# 411_Preliminary_Design__Group8_rev4_6.net
KiCad netlist of a schematic drawn in EAGLE
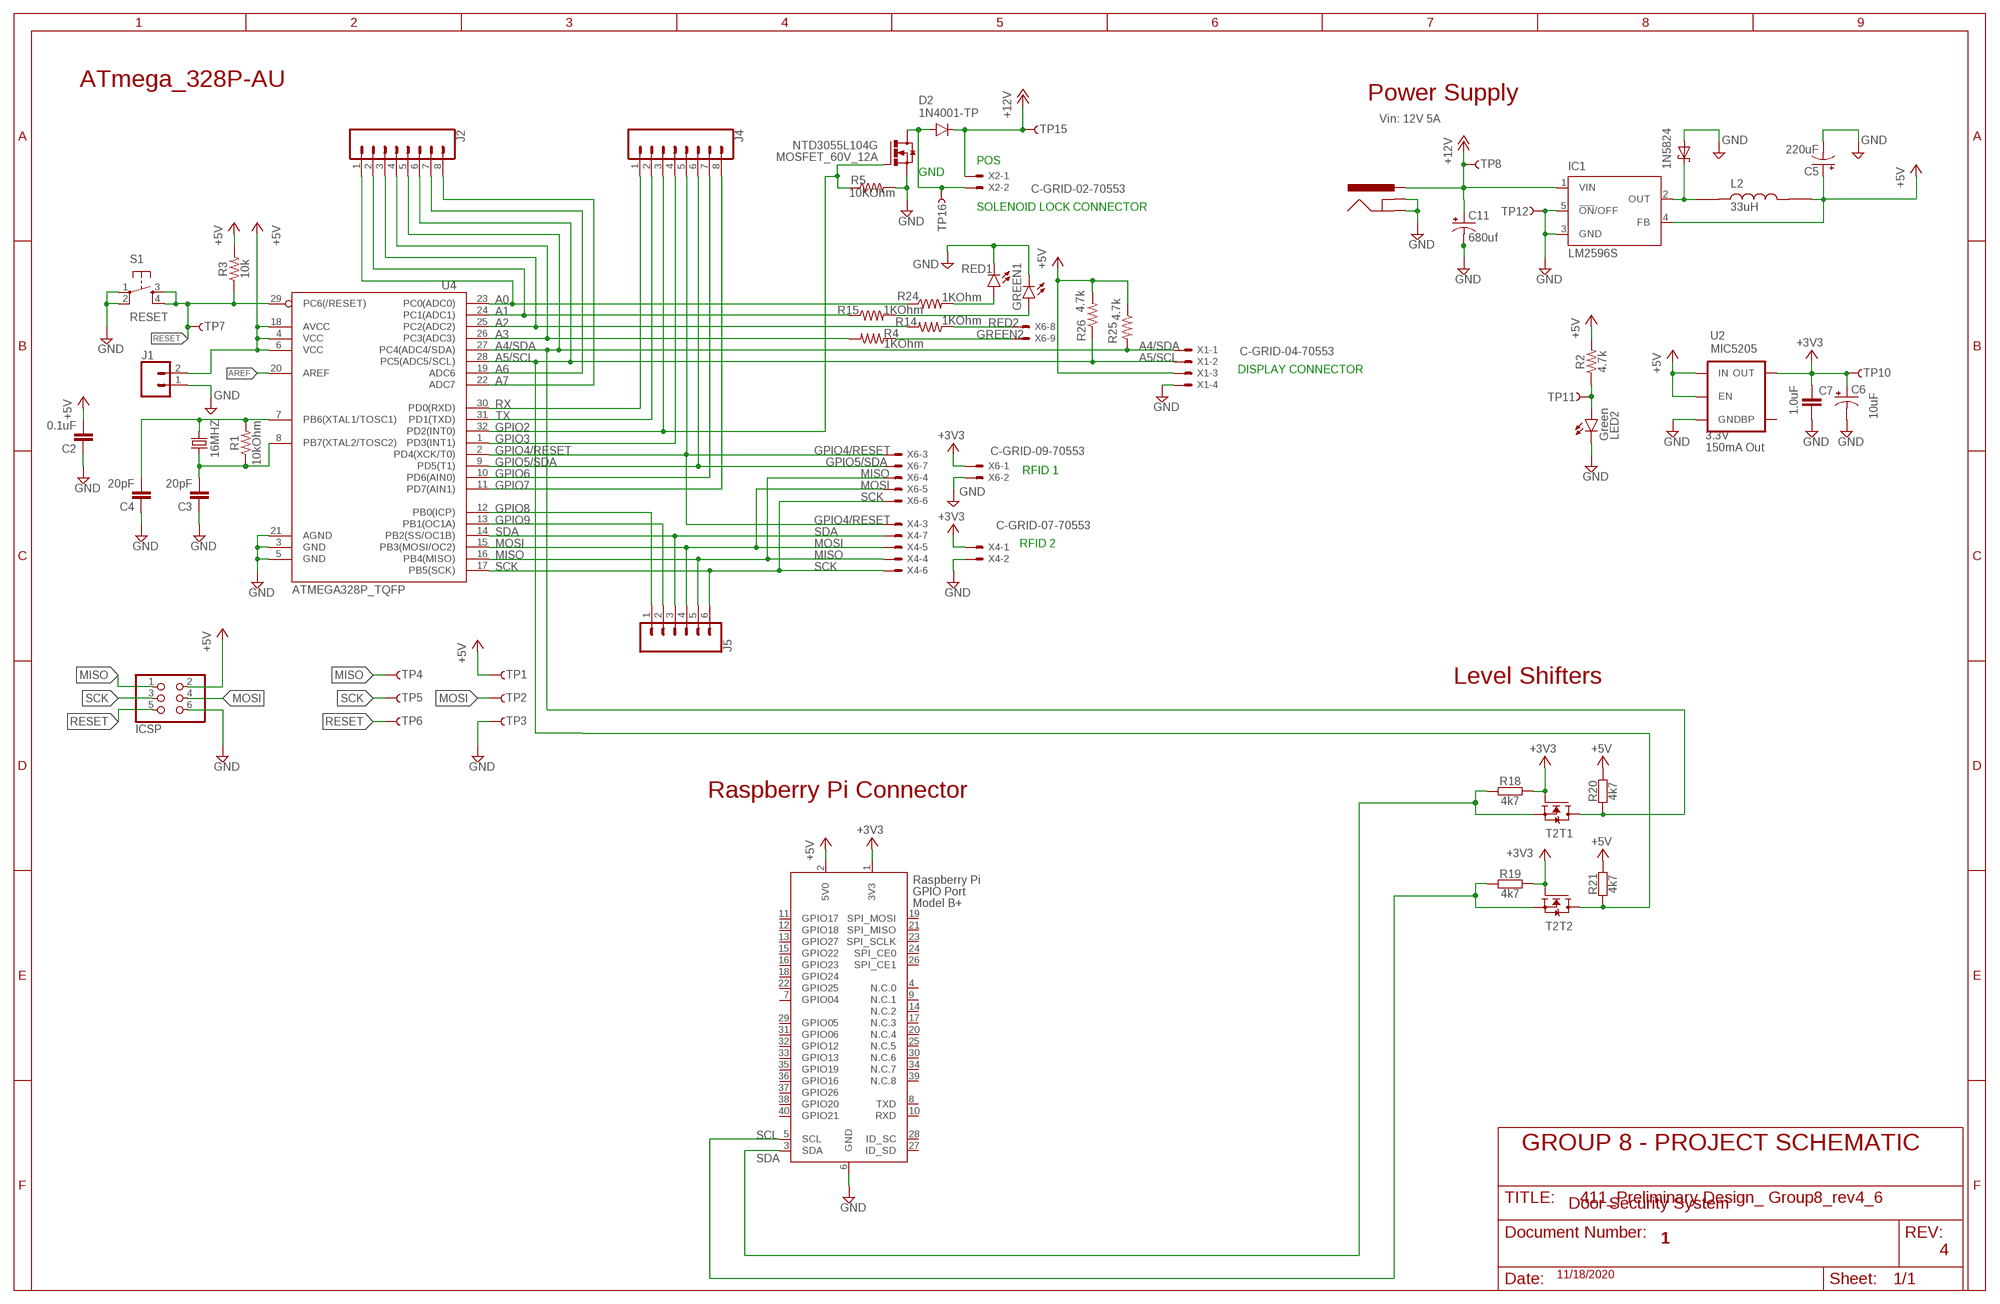
[diagram p0: schematic, sheet 1]

(export (version "E")
  (design (tool "Eeschema 10.0.6"))
  (components
    (comp (ref "1N5824")
      (value "SCHOTTKY-DIODECB429-15")
      (footprint "eagle-import:CB429-15")
      (libsource (lib "eagle-import") (part "SCHOTTKY-DIODECB429-15"))
    )
    (comp (ref "16MHZ")
      (value "16MHZ")
      (footprint "eagle-import:HC49_S")
      (libsource (lib "eagle-import") (part "CRYSTALHC49S"))
    )
    (comp (ref "C2")
      (value "0.1uF")
      (footprint "eagle-import:0603")
      (libsource (lib "eagle-import") (part "0.1UF-0603-25V-(+80/-20%)"))
    )
    (comp (ref "C3")
      (value "20pF")
      (footprint "eagle-import:0603")
      (libsource (lib "eagle-import") (part "0.1UF-0603-25V-(+80/-20%)"))
    )
    (comp (ref "C4")
      (value "20pF")
      (footprint "eagle-import:0603")
      (libsource (lib "eagle-import") (part "0.1UF-0603-25V-(+80/-20%)"))
    )
    (comp (ref "C5")
      (value "220uF")
      (footprint "eagle-import:153CLV-0605")
      (libsource (lib "eagle-import") (part "CPOL-US153CLV-0605"))
    )
    (comp (ref "C6")
      (value "10uF")
      (footprint "eagle-import:EIA3216")
      (libsource (lib "eagle-import") (part "10UF-POLAR-EIA3216-16V-10%(TANT)"))
    )
    (comp (ref "C7")
      (value "1.0uF")
      (footprint "eagle-import:0603")
      (libsource (lib "eagle-import") (part "1.0UF-0603-16V-10%"))
    )
    (comp (ref "C11")
      (value "680uf")
      (footprint "eagle-import:153CLV-0605")
      (libsource (lib "eagle-import") (part "CPOL-US153CLV-0605"))
    )
    (comp (ref "D2")
      (value "1N4001-TP")
      (footprint "eagle-import:DO41-10")
      (libsource (lib "eagle-import") (part "1N4004"))
    )
    (comp (ref "GREEN1")
      (value "LED5MM")
      (footprint "eagle-import:LED5MM")
      (libsource (lib "eagle-import") (part "led_259_LED5MM"))
    )
    (comp (ref "IC1")
      (value "LM2596S")
      (footprint "eagle-import:TO263-5")
      (fields (field (name "MF") "NATIONAL SEMICONDUCTOR") (field (name "MPN") "LM2596S-ADJ/NOPB"))
      (libsource (lib "eagle-import") (part "LM2596S"))
    )
    (comp (ref "ICSP")
      (value "ICSP")
      (footprint "eagle-import:2X03")
      (libsource (lib "eagle-import") (part "PINHD-2X3"))
    )
    (comp (ref "J1")
      (value "CONN_02")
      (footprint "eagle-import:1X02")
      (libsource (lib "eagle-import") (part "CONN_02"))
    )
    (comp (ref "J2")
      (value "CONN_08\"")
      (footprint "eagle-import:1X08")
      (libsource (lib "eagle-import") (part "CONN_08{dblquote}"))
    )
    (comp (ref "J3")
      (value "POWER_JACKSUPER_BOMB_DIGITY")
      (footprint "eagle-import:POWER_JACK_SMD_OVERPASTE_SUPER_BOMB_DIGITY")
      (libsource (lib "eagle-import") (part "POWER_JACKSUPER_BOMB_DIGITY"))
    )
    (comp (ref "J4")
      (value "CONN_08\"")
      (footprint "eagle-import:1X08")
      (libsource (lib "eagle-import") (part "CONN_08{dblquote}"))
    )
    (comp (ref "J5")
      (value "CONN_06SILK_FEMALE_PTH")
      (footprint "eagle-import:1X06")
      (libsource (lib "eagle-import") (part "CONN_06SILK_FEMALE_PTH"))
    )
    (comp (ref "L2")
      (value "33uH")
      (footprint "eagle-import:IND_#B953AS-330M=P3")
      (fields
        (field (name "DIGI-KEY_PART_NUMBER") "490-14099-1-ND")
        (field (name "MF") "Murata")
        (field (name "MP") "#B953AS-330M=P3")
      )
      (libsource (lib "eagle-import") (part "#B953AS-330M=P3"))
    )
    (comp (ref "LED2")
      (value "Green")
      (footprint "eagle-import:LED-1206")
      (libsource (lib "eagle-import") (part "LED1206"))
    )
    (comp (ref "MOSFET_60V_12A")
      (value "NTD3055L104G")
      (footprint "eagle-import:DPAK3")
      (fields (field (name "MANUFACTURER") "ON SEMICONDUCTORS") (field (name "CREATED_BY") "PCBLayout.com"))
      (libsource (lib "eagle-import") (part "NTD3055L104G"))
    )
    (comp (ref "R1")
      (value "10kOhm")
      (footprint "eagle-import:0603")
      (libsource (lib "eagle-import") (part "10KOHM-0603-1/10W-1%"))
    )
    (comp (ref "R2")
      (value "4.7k")
      (footprint "eagle-import:0603")
      (libsource (lib "eagle-import") (part "4.7KOHM-0603-1/10W-1%"))
    )
    (comp (ref "R3")
      (value "10k")
      (footprint "eagle-import:0603")
      (libsource (lib "eagle-import") (part "10KOHM-0603-1/10W-1%"))
    )
    (comp (ref "R4")
      (value "1KOhm")
      (footprint "eagle-import:M1406")
      (libsource (lib "eagle-import") (part "R-US_M1406"))
    )
    (comp (ref "R5")
      (value "10KOhm")
      (footprint "eagle-import:M1406")
      (libsource (lib "eagle-import") (part "R-US_M1406"))
    )
    (comp (ref "R14")
      (value "1KOhm")
      (footprint "eagle-import:M1406")
      (libsource (lib "eagle-import") (part "R-US_M1406"))
    )
    (comp (ref "R15")
      (value "1KOhm")
      (footprint "eagle-import:M1406")
      (libsource (lib "eagle-import") (part "R-US_M1406"))
    )
    (comp (ref "R18")
      (value "4k7")
      (footprint "eagle-import:C0402")
      (libsource (lib "eagle-import") (part "RESISTOR-0402"))
    )
    (comp (ref "R19")
      (value "4k7")
      (footprint "eagle-import:C0402")
      (libsource (lib "eagle-import") (part "RESISTOR-0402"))
    )
    (comp (ref "R20")
      (value "4k7")
      (footprint "eagle-import:C0402")
      (libsource (lib "eagle-import") (part "RESISTOR-0402"))
    )
    (comp (ref "R21")
      (value "4k7")
      (footprint "eagle-import:C0402")
      (libsource (lib "eagle-import") (part "RESISTOR-0402"))
    )
    (comp (ref "R24")
      (value "1KOhm")
      (footprint "eagle-import:M1406")
      (libsource (lib "eagle-import") (part "R-US_M1406"))
    )
    (comp (ref "R25")
      (value "4.7k")
      (footprint "eagle-import:0603")
      (libsource (lib "eagle-import") (part "4.7KOHM-0603-1/10W-1%"))
    )
    (comp (ref "R26")
      (value "4.7k")
      (footprint "eagle-import:0603")
      (libsource (lib "eagle-import") (part "4.7KOHM-0603-1/10W-1%"))
    )
    (comp (ref "RED1")
      (value "LED5MM")
      (footprint "eagle-import:LED5MM")
      (fields (field (name "SPICEPREFIX") "L"))
      (libsource (lib "eagle-import") (part "led_259_LED5MM"))
    )
    (comp (ref "S1")
      (value "RESET")
      (footprint "eagle-import:TACTILE-SWITCH-SMD")
      (libsource (lib "eagle-import") (part "SWITCH_SPST_4_PINSQUARE"))
    )
    (comp (ref "T2")
      (value "BSS138PS")
      (footprint "eagle-import:SOT363")
      (libsource (lib "eagle-import") (part "BSS138PS"))
    )
    (comp (ref "TP1")
      (value "TP-3x5")
      (footprint "eagle-import:PAD.03X.05")
      (libsource (lib "eagle-import") (part "TEST-POINT3X5"))
    )
    (comp (ref "TP2")
      (value "TP-3x5")
      (footprint "eagle-import:PAD.03X.05")
      (libsource (lib "eagle-import") (part "TEST-POINT3X5"))
    )
    (comp (ref "TP3")
      (value "TP-3x5")
      (footprint "eagle-import:PAD.03X.05")
      (libsource (lib "eagle-import") (part "TEST-POINT3X5"))
    )
    (comp (ref "TP4")
      (value "TP-3x5")
      (footprint "eagle-import:PAD.03X.05")
      (libsource (lib "eagle-import") (part "TEST-POINT3X5"))
    )
    (comp (ref "TP5")
      (value "TP-3x5")
      (footprint "eagle-import:PAD.03X.05")
      (libsource (lib "eagle-import") (part "SparkFun-Passives_TEST-POINT3X5"))
    )
    (comp (ref "TP6")
      (value "TP-3x5")
      (footprint "eagle-import:PAD.03X.05")
      (libsource (lib "eagle-import") (part "TEST-POINT3X5"))
    )
    (comp (ref "TP7")
      (value "TP-3x5")
      (footprint "eagle-import:PAD.03X.05")
      (libsource (lib "eagle-import") (part "TEST-POINT3X5"))
    )
    (comp (ref "TP8")
      (value "TP-3x5")
      (footprint "eagle-import:PAD.03X.05")
      (libsource (lib "eagle-import") (part "TEST-POINT3X5"))
    )
    (comp (ref "TP10")
      (value "TP-3x5")
      (footprint "eagle-import:PAD.03X.05")
      (libsource (lib "eagle-import") (part "TEST-POINT3X5"))
    )
    (comp (ref "TP11")
      (value "TP-3x5")
      (footprint "eagle-import:PAD.03X.05")
      (libsource (lib "eagle-import") (part "TEST-POINT3X5"))
    )
    (comp (ref "TP12")
      (value "TP-3x5")
      (footprint "eagle-import:PAD.03X.05")
      (libsource (lib "eagle-import") (part "TEST-POINT3X5"))
    )
    (comp (ref "TP15")
      (value "TP-3x5")
      (footprint "eagle-import:PAD.03X.05")
      (libsource (lib "eagle-import") (part "TEST-POINT3X5"))
    )
    (comp (ref "TP16")
      (value "TP-3x5")
      (footprint "eagle-import:PAD.03X.05")
      (libsource (lib "eagle-import") (part "TEST-POINT3X5"))
    )
    (comp (ref "U2")
      (value "MIC5205")
      (footprint "eagle-import:SOT23-5")
      (libsource (lib "eagle-import") (part "MIC52053.3V"))
    )
    (comp (ref "U4")
      (value "ATMEGA328P_TQFP")
      (footprint "eagle-import:TQFP32-08")
      (libsource (lib "eagle-import") (part "ATMEGA328P_TQFP"))
    )
    (comp (ref "X1")
      (value "C-GRID-04-70553")
      (footprint "eagle-import:70553-04")
      (fields (field (name "MF") "MOLEX"))
      (libsource (lib "eagle-import") (part "C-GRID-04-70553"))
    )
    (comp (ref "X2")
      (value "C-GRID-02-70553")
      (footprint "eagle-import:70553-02")
      (fields (field (name "MF") "MOLEX"))
      (libsource (lib "eagle-import") (part "C-GRID-02-70553"))
    )
    (comp (ref "X4")
      (value "C-GRID-07-70553")
      (footprint "eagle-import:70553-07")
      (fields (field (name "MF") "MOLEX"))
      (libsource (lib "eagle-import") (part "C-GRID-07-70553"))
    )
    (comp (ref "X5")
      (value "RASPI_BOARD_B+_E4P")
      (footprint "eagle-import:RASPI_BOARD_B+_EDGES_4DRILL_PAD")
      (libsource (lib "eagle-import") (part "RASPI_BOARD_B+_E4P"))
    )
    (comp (ref "X6")
      (value "C-GRID-09-70553")
      (footprint "eagle-import:70553-09")
      (fields (field (name "MF") "MOLEX"))
      (libsource (lib "eagle-import") (part "C-GRID-09-70553"))
    )
  )
  (nets
    (net (code "1") (name "+3V3") (class "Default")
      (node (ref "C6") (pin "+") (pinfunction "+_+") (pintype "passive"))
      (node (ref "C7") (pin "1") (pinfunction "1_1") (pintype "passive"))
      (node (ref "R18") (pin "2") (pinfunction "2_2") (pintype "passive"))
      (node (ref "R19") (pin "2") (pinfunction "2_2") (pintype "passive"))
      (node (ref "T2") (pin "2") (pinfunction "G_2") (pintype "passive"))
      (node (ref "T2") (pin "5") (pinfunction "G_5") (pintype "passive"))
      (node (ref "TP10") (pin "P$1") (pinfunction "1_P$1") (pintype "bidirectional"))
      (node (ref "U2") (pin "5") (pinfunction "OUT_5") (pintype "passive"))
      (node (ref "X4") (pin "1") (pinfunction "S_1") (pintype "passive"))
      (node (ref "X5") (pin "1") (pinfunction "3V3_1") (pintype "power_in"))
      (node (ref "X6") (pin "1") (pinfunction "S_1") (pintype "passive"))
    )
    (net (code "2") (name "+5V") (class "Default")
      (node (ref "C2") (pin "2") (pinfunction "2_2") (pintype "passive"))
      (node (ref "C5") (pin "+") (pinfunction "+_+") (pintype "passive"))
      (node (ref "IC1") (pin "4") (pinfunction "FB_4") (pintype "input"))
      (node (ref "ICSP") (pin "2") (pinfunction "2_2") (pintype "passive"))
      (node (ref "J1") (pin "2") (pinfunction "2_2") (pintype "passive"))
      (node (ref "L2") (pin "2") (pinfunction "2_2") (pintype "passive"))
      (node (ref "R2") (pin "2") (pinfunction "2_2") (pintype "passive"))
      (node (ref "R20") (pin "2") (pinfunction "2_2") (pintype "passive"))
      (node (ref "R21") (pin "2") (pinfunction "2_2") (pintype "passive"))
      (node (ref "R25") (pin "1") (pinfunction "1_1") (pintype "passive"))
      (node (ref "R26") (pin "2") (pinfunction "2_2") (pintype "passive"))
      (node (ref "R3") (pin "2") (pinfunction "2_2") (pintype "passive"))
      (node (ref "TP1") (pin "P$1") (pinfunction "1_P$1") (pintype "bidirectional"))
      (node (ref "U2") (pin "1") (pinfunction "IN_1") (pintype "input"))
      (node (ref "U2") (pin "3") (pinfunction "EN_3") (pintype "input"))
      (node (ref "U4") (pin "18") (pinfunction "AVCC_18") (pintype "bidirectional"))
      (node (ref "U4") (pin "4") (pinfunction "VCC_4") (pintype "bidirectional"))
      (node (ref "U4") (pin "6") (pinfunction "VCC_6") (pintype "bidirectional"))
      (node (ref "X1") (pin "3") (pinfunction "S_3") (pintype "passive"))
      (node (ref "X5") (pin "2") (pinfunction "5V0_2") (pintype "power_in"))
    )
    (net (code "3") (name "+12V") (class "Default")
      (node (ref "C11") (pin "+") (pinfunction "+_+") (pintype "passive"))
      (node (ref "D2") (pin "C") (pinfunction "C_C") (pintype "passive"))
      (node (ref "IC1") (pin "1") (pinfunction "VIN_1") (pintype "input"))
      (node (ref "J3") (pin "VIN0") (pinfunction "PWR_VIN0") (pintype "bidirectional"))
      (node (ref "TP15") (pin "P$1") (pinfunction "1_P$1") (pintype "bidirectional"))
      (node (ref "TP8") (pin "P$1") (pinfunction "1_P$1") (pintype "bidirectional"))
      (node (ref "X2") (pin "1") (pinfunction "S_1") (pintype "passive"))
    )
    (net (code "4") (name "/A0") (class "Default")
      (node (ref "J2") (pin "1") (pinfunction "1_1") (pintype "passive"))
      (node (ref "R24") (pin "1") (pinfunction "1_1") (pintype "passive"))
      (node (ref "U4") (pin "23") (pinfunction "PC0(ADC0)_23") (pintype "bidirectional"))
    )
    (net (code "5") (name "/A1") (class "Default")
      (node (ref "J2") (pin "2") (pinfunction "2_2") (pintype "passive"))
      (node (ref "R15") (pin "1") (pinfunction "1_1") (pintype "passive"))
      (node (ref "U4") (pin "24") (pinfunction "PC1(ADC1)_24") (pintype "bidirectional"))
    )
    (net (code "6") (name "/A2") (class "Default")
      (node (ref "J2") (pin "3") (pinfunction "3_3") (pintype "passive"))
      (node (ref "R14") (pin "2") (pinfunction "2_2") (pintype "passive"))
      (node (ref "U4") (pin "25") (pinfunction "PC2(ADC2)_25") (pintype "bidirectional"))
    )
    (net (code "7") (name "/A3") (class "Default")
      (node (ref "J2") (pin "4") (pinfunction "4_4") (pintype "passive"))
      (node (ref "R4") (pin "2") (pinfunction "2_2") (pintype "passive"))
      (node (ref "U4") (pin "26") (pinfunction "PC3(ADC3)_26") (pintype "bidirectional"))
    )
    (net (code "8") (name "/A4{slash}SDA") (class "Default")
      (node (ref "J2") (pin "5") (pinfunction "5_5") (pintype "passive"))
      (node (ref "R20") (pin "1") (pinfunction "1_1") (pintype "passive"))
      (node (ref "R25") (pin "2") (pinfunction "2_2") (pintype "passive"))
      (node (ref "T2") (pin "6") (pinfunction "D_6") (pintype "passive"))
      (node (ref "U4") (pin "27") (pinfunction "PC4(ADC4/SDA)_27") (pintype "bidirectional"))
      (node (ref "X1") (pin "1") (pinfunction "S_1") (pintype "passive"))
    )
    (net (code "9") (name "/A5{slash}SCL") (class "Default")
      (node (ref "J2") (pin "6") (pinfunction "6_6") (pintype "passive"))
      (node (ref "R21") (pin "1") (pinfunction "1_1") (pintype "passive"))
      (node (ref "R26") (pin "1") (pinfunction "1_1") (pintype "passive"))
      (node (ref "T2") (pin "3") (pinfunction "D_3") (pintype "passive"))
      (node (ref "U4") (pin "28") (pinfunction "PC5(ADC5/SCL)_28") (pintype "bidirectional"))
      (node (ref "X1") (pin "2") (pinfunction "S_2") (pintype "passive"))
    )
    (net (code "10") (name "/A6") (class "Default")
      (node (ref "J2") (pin "7") (pinfunction "7_7") (pintype "passive"))
      (node (ref "U4") (pin "19") (pinfunction "ADC6_19") (pintype "bidirectional"))
    )
    (net (code "11") (name "/A7") (class "Default")
      (node (ref "J2") (pin "8") (pinfunction "8_8") (pintype "passive"))
      (node (ref "U4") (pin "22") (pinfunction "ADC7_22") (pintype "bidirectional"))
    )
    (net (code "12") (name "/GPIO2") (class "Default")
      (node (ref "J4") (pin "3") (pinfunction "3_3") (pintype "passive"))
      (node (ref "MOSFET_60V_12A") (pin "1") (pinfunction "G_1") (pintype "passive"))
      (node (ref "R5") (pin "1") (pinfunction "1_1") (pintype "passive"))
      (node (ref "U4") (pin "32") (pinfunction "PD2(INT0)_32") (pintype "bidirectional"))
    )
    (net (code "13") (name "/GPIO3") (class "Default")
      (node (ref "J4") (pin "4") (pinfunction "4_4") (pintype "passive"))
      (node (ref "U4") (pin "1") (pinfunction "PD3(INT1)_1") (pintype "bidirectional"))
    )
    (net (code "14") (name "/GPIO4{slash}RESET") (class "Default")
      (node (ref "J4") (pin "5") (pinfunction "5_5") (pintype "passive"))
      (node (ref "U4") (pin "2") (pinfunction "PD4(XCK/T0)_2") (pintype "bidirectional"))
      (node (ref "X4") (pin "3") (pinfunction "S_3") (pintype "passive"))
      (node (ref "X6") (pin "3") (pinfunction "S_3") (pintype "passive"))
    )
    (net (code "15") (name "/GPIO5{slash}SDA") (class "Default")
      (node (ref "J4") (pin "6") (pinfunction "6_6") (pintype "passive"))
      (node (ref "U4") (pin "9") (pinfunction "PD5(T1)_9") (pintype "bidirectional"))
      (node (ref "X6") (pin "7") (pinfunction "S_7") (pintype "passive"))
    )
    (net (code "16") (name "/GPIO6") (class "Default")
      (node (ref "J4") (pin "7") (pinfunction "7_7") (pintype "passive"))
      (node (ref "U4") (pin "10") (pinfunction "PD6(AIN0)_10") (pintype "bidirectional"))
    )
    (net (code "17") (name "/GPIO7") (class "Default")
      (node (ref "J4") (pin "8") (pinfunction "8_8") (pintype "passive"))
      (node (ref "U4") (pin "11") (pinfunction "PD7(AIN1)_11") (pintype "bidirectional"))
    )
    (net (code "18") (name "/GPIO8") (class "Default")
      (node (ref "J5") (pin "1") (pinfunction "1_1") (pintype "passive"))
      (node (ref "U4") (pin "12") (pinfunction "PB0(ICP)_12") (pintype "bidirectional"))
    )
    (net (code "19") (name "/GPIO9") (class "Default")
      (node (ref "J5") (pin "2") (pinfunction "2_2") (pintype "passive"))
      (node (ref "U4") (pin "13") (pinfunction "PB1(OC1A)_13") (pintype "bidirectional"))
    )
    (net (code "20") (name "/GREEN2") (class "Default")
      (node (ref "R4") (pin "1") (pinfunction "1_1") (pintype "passive"))
      (node (ref "X6") (pin "9") (pinfunction "S_9") (pintype "passive"))
    )
    (net (code "21") (name "/RED2") (class "Default")
      (node (ref "R14") (pin "1") (pinfunction "1_1") (pintype "passive"))
      (node (ref "X6") (pin "8") (pinfunction "S_8") (pintype "passive"))
    )
    (net (code "22") (name "/RX") (class "Default")
      (node (ref "J4") (pin "1") (pinfunction "1_1") (pintype "passive"))
      (node (ref "U4") (pin "30") (pinfunction "PD0(RXD)_30") (pintype "bidirectional"))
    )
    (net (code "23") (name "/SCL") (class "Default")
      (node (ref "R19") (pin "1") (pinfunction "1_1") (pintype "passive"))
      (node (ref "T2") (pin "4") (pinfunction "S_4") (pintype "passive"))
      (node (ref "X5") (pin "5") (pinfunction "SCL_5") (pintype "bidirectional"))
    )
    (net (code "24") (name "/SDA") (class "Default")
      (node (ref "J5") (pin "3") (pinfunction "3_3") (pintype "passive"))
      (node (ref "R18") (pin "1") (pinfunction "1_1") (pintype "passive"))
      (node (ref "T2") (pin "1") (pinfunction "S_1") (pintype "passive"))
      (node (ref "U4") (pin "14") (pinfunction "PB2(SS/OC1B)_14") (pintype "bidirectional"))
      (node (ref "X4") (pin "7") (pinfunction "S_7") (pintype "passive"))
      (node (ref "X5") (pin "3") (pinfunction "SDA_3") (pintype "bidirectional"))
    )
    (net (code "25") (name "/TX") (class "Default")
      (node (ref "J4") (pin "2") (pinfunction "2_2") (pintype "passive"))
      (node (ref "U4") (pin "31") (pinfunction "PD1(TXD)_31") (pintype "bidirectional"))
    )
    (net (code "26") (name "AREF") (class "Default")
      (node (ref "U4") (pin "20") (pinfunction "AREF_20") (pintype "bidirectional"))
    )
    (net (code "27") (name "GND") (class "Default")
      (node (ref "1N5824") (pin "A") (pinfunction "A_A") (pintype "passive"))
      (node (ref "C11") (pin "-") (pinfunction "-_-") (pintype "passive"))
      (node (ref "C2") (pin "1") (pinfunction "1_1") (pintype "passive"))
      (node (ref "C3") (pin "1") (pinfunction "1_1") (pintype "passive"))
      (node (ref "C4") (pin "1") (pinfunction "1_1") (pintype "passive"))
      (node (ref "C5") (pin "-") (pinfunction "-_-") (pintype "passive"))
      (node (ref "C6") (pin "-") (pinfunction "-_-") (pintype "passive"))
      (node (ref "C7") (pin "2") (pinfunction "2_2") (pintype "passive"))
      (node (ref "GREEN1") (pin "K") (pinfunction "C_K") (pintype "passive"))
      (node (ref "IC1") (pin "3") (pinfunction "GND_3") (pintype "power_in"))
      (node (ref "IC1") (pin "5") (pinfunction "~{ON}/OFF_5") (pintype "input"))
      (node (ref "ICSP") (pin "6") (pinfunction "6_6") (pintype "passive"))
      (node (ref "J1") (pin "1") (pinfunction "1_1") (pintype "passive"))
      (node (ref "J3") (pin "GND") (pinfunction "GNDBREAK_GND") (pintype "bidirectional"))
      (node (ref "J3") (pin "P$4") (pinfunction "GND_P$4") (pintype "bidirectional"))
      (node (ref "LED2") (pin "C") (pinfunction "C_C") (pintype "passive"))
      (node (ref "MOSFET_60V_12A") (pin "2") (pinfunction "S_2") (pintype "passive"))
      (node (ref "R5") (pin "2") (pinfunction "2_2") (pintype "passive"))
      (node (ref "RED1") (pin "K") (pinfunction "C_K") (pintype "passive"))
      (node (ref "S1") (pin "1") (pinfunction "1_1") (pintype "passive"))
      (node (ref "S1") (pin "2") (pinfunction "2_2") (pintype "passive"))
      (node (ref "TP12") (pin "P$1") (pinfunction "1_P$1") (pintype "bidirectional"))
      (node (ref "TP3") (pin "P$1") (pinfunction "1_P$1") (pintype "bidirectional"))
      (node (ref "U2") (pin "2") (pinfunction "GND_2") (pintype "input"))
      (node (ref "U4") (pin "21") (pinfunction "AGND_21") (pintype "bidirectional"))
      (node (ref "U4") (pin "3") (pinfunction "GND_3") (pintype "bidirectional"))
      (node (ref "U4") (pin "5") (pinfunction "GND_5") (pintype "bidirectional"))
      (node (ref "X1") (pin "4") (pinfunction "S_4") (pintype "passive"))
      (node (ref "X4") (pin "2") (pinfunction "S_2") (pintype "passive"))
      (node (ref "X5") (pin "6") (pinfunction "GND_6") (pintype "power_in"))
      (node (ref "X6") (pin "2") (pinfunction "S_2") (pintype "passive"))
    )
    (net (code "28") (name "MISO") (class "Default")
      (node (ref "ICSP") (pin "1") (pinfunction "1_1") (pintype "passive"))
      (node (ref "J5") (pin "5") (pinfunction "5_5") (pintype "passive"))
      (node (ref "TP4") (pin "P$1") (pinfunction "1_P$1") (pintype "bidirectional"))
      (node (ref "U4") (pin "16") (pinfunction "PB4(MISO)_16") (pintype "bidirectional"))
      (node (ref "X4") (pin "4") (pinfunction "S_4") (pintype "passive"))
      (node (ref "X6") (pin "4") (pinfunction "S_4") (pintype "passive"))
    )
    (net (code "29") (name "MOSI") (class "Default")
      (node (ref "ICSP") (pin "4") (pinfunction "4_4") (pintype "passive"))
      (node (ref "J5") (pin "4") (pinfunction "4_4") (pintype "passive"))
      (node (ref "TP2") (pin "P$1") (pinfunction "1_P$1") (pintype "bidirectional"))
      (node (ref "U4") (pin "15") (pinfunction "PB3(MOSI/OC2)_15") (pintype "bidirectional"))
      (node (ref "X4") (pin "5") (pinfunction "S_5") (pintype "passive"))
      (node (ref "X6") (pin "5") (pinfunction "S_5") (pintype "passive"))
    )
    (net (code "30") (name "Net-(GREEN1-PadA)") (class "Default")
      (node (ref "GREEN1") (pin "A") (pinfunction "A_A") (pintype "passive"))
      (node (ref "R15") (pin "2") (pinfunction "2_2") (pintype "passive"))
    )
    (net (code "31") (name "Net-(IC1-OUT)") (class "Default")
      (node (ref "1N5824") (pin "C") (pinfunction "C_C") (pintype "passive"))
      (node (ref "IC1") (pin "2") (pinfunction "OUT_2") (pintype "output"))
      (node (ref "L2") (pin "1") (pinfunction "1_1") (pintype "passive"))
    )
    (net (code "32") (name "Net-(MOSFET_60V_12A-D)") (class "Default")
      (node (ref "D2") (pin "A") (pinfunction "A_A") (pintype "passive"))
      (node (ref "MOSFET_60V_12A") (pin "3") (pinfunction "D_3") (pintype "passive"))
      (node (ref "TP16") (pin "P$1") (pinfunction "1_P$1") (pintype "bidirectional"))
      (node (ref "X2") (pin "2") (pinfunction "S_2") (pintype "passive"))
    )
    (net (code "33") (name "Net-(R24-Pad2)") (class "Default")
      (node (ref "R24") (pin "2") (pinfunction "2_2") (pintype "passive"))
      (node (ref "RED1") (pin "A") (pinfunction "A_A") (pintype "passive"))
    )
    (net (code "34") (name "Net-(TP11-1)") (class "Default")
      (node (ref "LED2") (pin "A") (pinfunction "A_A") (pintype "passive"))
      (node (ref "R2") (pin "1") (pinfunction "1_1") (pintype "passive"))
      (node (ref "TP11") (pin "P$1") (pinfunction "1_P$1") (pintype "bidirectional"))
    )
    (net (code "35") (name "Net-(U4-PB6(XTAL1{slash}TOSC1))") (class "Default")
      (node (ref "16MHZ") (pin "2") (pinfunction "2_2") (pintype "passive"))
      (node (ref "C4") (pin "2") (pinfunction "2_2") (pintype "passive"))
      (node (ref "R1") (pin "2") (pinfunction "2_2") (pintype "passive"))
      (node (ref "U4") (pin "7") (pinfunction "PB6(XTAL1/TOSC1)_7") (pintype "bidirectional"))
    )
    (net (code "36") (name "Net-(U4-PB7(XTAL2{slash}TOSC2))") (class "Default")
      (node (ref "16MHZ") (pin "1") (pinfunction "1_1") (pintype "passive"))
      (node (ref "C3") (pin "2") (pinfunction "2_2") (pintype "passive"))
      (node (ref "R1") (pin "1") (pinfunction "1_1") (pintype "passive"))
      (node (ref "U4") (pin "8") (pinfunction "PB7(XTAL2/TOSC2)_8") (pintype "bidirectional"))
    )
    (net (code "37") (name "RESET") (class "Default")
      (node (ref "ICSP") (pin "5") (pinfunction "5_5") (pintype "passive"))
      (node (ref "R3") (pin "1") (pinfunction "1_1") (pintype "passive"))
      (node (ref "S1") (pin "3") (pinfunction "3_3") (pintype "passive"))
      (node (ref "S1") (pin "4") (pinfunction "4_4") (pintype "passive"))
      (node (ref "TP6") (pin "P$1") (pinfunction "1_P$1") (pintype "bidirectional"))
      (node (ref "TP7") (pin "P$1") (pinfunction "1_P$1") (pintype "bidirectional"))
      (node (ref "U4") (pin "29") (pinfunction "PC6(/RESET)_29") (pintype "bidirectional"))
    )
    (net (code "38") (name "SCK") (class "Default")
      (node (ref "ICSP") (pin "3") (pinfunction "3_3") (pintype "passive"))
      (node (ref "J5") (pin "6") (pinfunction "6_6") (pintype "passive"))
      (node (ref "TP5") (pin "P$1") (pinfunction "1_P$1") (pintype "bidirectional"))
      (node (ref "U4") (pin "17") (pinfunction "PB5(SCK)_17") (pintype "bidirectional"))
      (node (ref "X4") (pin "6") (pinfunction "S_6") (pintype "passive"))
      (node (ref "X6") (pin "6") (pinfunction "S_6") (pintype "passive"))
    )
    (net (code "39") (name "unconnected-(U2-BP-Pad4)") (class "Default")
      (node (ref "U2") (pin "4") (pinfunction "BP_4") (pintype "input"))
    )
    (net (code "40") (name "unconnected-(X5-GPIO04-Pad7)") (class "Default")
      (node (ref "X5") (pin "7") (pinfunction "GPIO04_7") (pintype "bidirectional"))
    )
    (net (code "41") (name "unconnected-(X5-GPIO05-Pad29)") (class "Default")
      (node (ref "X5") (pin "29") (pinfunction "GPIO05_29") (pintype "no_connect"))
    )
    (net (code "42") (name "unconnected-(X5-GPIO06-Pad31)") (class "Default")
      (node (ref "X5") (pin "31") (pinfunction "GPIO06_31") (pintype "no_connect"))
    )
    (net (code "43") (name "unconnected-(X5-GPIO12-Pad32)") (class "Default")
      (node (ref "X5") (pin "32") (pinfunction "GPIO12_32") (pintype "no_connect"))
    )
    (net (code "44") (name "unconnected-(X5-GPIO13-Pad33)") (class "Default")
      (node (ref "X5") (pin "33") (pinfunction "GPIO13_33") (pintype "no_connect"))
    )
    (net (code "45") (name "unconnected-(X5-GPIO16-Pad36)") (class "Default")
      (node (ref "X5") (pin "36") (pinfunction "GPIO16_36") (pintype "no_connect"))
    )
    (net (code "46") (name "unconnected-(X5-GPIO17-Pad11)") (class "Default")
      (node (ref "X5") (pin "11") (pinfunction "GPIO17_11") (pintype "bidirectional"))
    )
    (net (code "47") (name "unconnected-(X5-GPIO18-Pad12)") (class "Default")
      (node (ref "X5") (pin "12") (pinfunction "GPIO18_12") (pintype "bidirectional"))
    )
    (net (code "48") (name "unconnected-(X5-GPIO19-Pad35)") (class "Default")
      (node (ref "X5") (pin "35") (pinfunction "GPIO19_35") (pintype "no_connect"))
    )
    (net (code "49") (name "unconnected-(X5-GPIO20-Pad38)") (class "Default")
      (node (ref "X5") (pin "38") (pinfunction "GPIO20_38") (pintype "no_connect"))
    )
    (net (code "50") (name "unconnected-(X5-GPIO21-Pad40)") (class "Default")
      (node (ref "X5") (pin "40") (pinfunction "GPIO21_40") (pintype "no_connect"))
    )
    (net (code "51") (name "unconnected-(X5-GPIO22-Pad15)") (class "Default")
      (node (ref "X5") (pin "15") (pinfunction "GPIO22_15") (pintype "bidirectional"))
    )
    (net (code "52") (name "unconnected-(X5-GPIO23-Pad16)") (class "Default")
      (node (ref "X5") (pin "16") (pinfunction "GPIO23_16") (pintype "bidirectional"))
    )
    (net (code "53") (name "unconnected-(X5-GPIO24-Pad18)") (class "Default")
      (node (ref "X5") (pin "18") (pinfunction "GPIO24_18") (pintype "bidirectional"))
    )
    (net (code "54") (name "unconnected-(X5-GPIO25-Pad22)") (class "Default")
      (node (ref "X5") (pin "22") (pinfunction "GPIO25_22") (pintype "bidirectional"))
    )
    (net (code "55") (name "unconnected-(X5-GPIO26-Pad37)") (class "Default")
      (node (ref "X5") (pin "37") (pinfunction "GPIO26_37") (pintype "no_connect"))
    )
    (net (code "56") (name "unconnected-(X5-GPIO27-Pad13)") (class "Default")
      (node (ref "X5") (pin "13") (pinfunction "GPIO27_13") (pintype "bidirectional"))
    )
    (net (code "57") (name "unconnected-(X5-ID_SC-Pad28)") (class "Default")
      (node (ref "X5") (pin "28") (pinfunction "ID_SC_28") (pintype "no_connect"))
    )
    (net (code "58") (name "unconnected-(X5-ID_SD-Pad27)") (class "Default")
      (node (ref "X5") (pin "27") (pinfunction "ID_SD_27") (pintype "no_connect"))
    )
    (net (code "59") (name "unconnected-(X5-N.C.0-Pad4)") (class "Default")
      (node (ref "X5") (pin "4") (pinfunction "N.C.0_4") (pintype "no_connect"))
    )
    (net (code "60") (name "unconnected-(X5-N.C.1-Pad9)") (class "Default")
      (node (ref "X5") (pin "9") (pinfunction "N.C.1_9") (pintype "no_connect"))
    )
    (net (code "61") (name "unconnected-(X5-N.C.2-Pad14)") (class "Default")
      (node (ref "X5") (pin "14") (pinfunction "N.C.2_14") (pintype "no_connect"))
    )
    (net (code "62") (name "unconnected-(X5-N.C.3-Pad17)") (class "Default")
      (node (ref "X5") (pin "17") (pinfunction "N.C.3_17") (pintype "no_connect"))
    )
    (net (code "63") (name "unconnected-(X5-N.C.4-Pad20)") (class "Default")
      (node (ref "X5") (pin "20") (pinfunction "N.C.4_20") (pintype "no_connect"))
    )
    (net (code "64") (name "unconnected-(X5-N.C.5-Pad25)") (class "Default")
      (node (ref "X5") (pin "25") (pinfunction "N.C.5_25") (pintype "no_connect"))
    )
    (net (code "65") (name "unconnected-(X5-N.C.6-Pad30)") (class "Default")
      (node (ref "X5") (pin "30") (pinfunction "N.C.6_30") (pintype "no_connect"))
    )
    (net (code "66") (name "unconnected-(X5-N.C.7-Pad34)") (class "Default")
      (node (ref "X5") (pin "34") (pinfunction "N.C.7_34") (pintype "no_connect"))
    )
    (net (code "67") (name "unconnected-(X5-N.C.8-Pad39)") (class "Default")
      (node (ref "X5") (pin "39") (pinfunction "N.C.8_39") (pintype "no_connect"))
    )
    (net (code "68") (name "unconnected-(X5-RXD-Pad10)") (class "Default")
      (node (ref "X5") (pin "10") (pinfunction "RXD_10") (pintype "bidirectional"))
    )
    (net (code "69") (name "unconnected-(X5-SPI_CE0-Pad24)") (class "Default")
      (node (ref "X5") (pin "24") (pinfunction "SPI_CE0_24") (pintype "bidirectional"))
    )
    (net (code "70") (name "unconnected-(X5-SPI_CE1-Pad26)") (class "Default")
      (node (ref "X5") (pin "26") (pinfunction "SPI_CE1_26") (pintype "bidirectional"))
    )
    (net (code "71") (name "unconnected-(X5-SPI_MISO-Pad21)") (class "Default")
      (node (ref "X5") (pin "21") (pinfunction "SPI_MISO_21") (pintype "bidirectional"))
    )
    (net (code "72") (name "unconnected-(X5-SPI_MOSI-Pad19)") (class "Default")
      (node (ref "X5") (pin "19") (pinfunction "SPI_MOSI_19") (pintype "bidirectional"))
    )
    (net (code "73") (name "unconnected-(X5-SPI_SCLK-Pad23)") (class "Default")
      (node (ref "X5") (pin "23") (pinfunction "SPI_SCLK_23") (pintype "bidirectional"))
    )
    (net (code "74") (name "unconnected-(X5-TXD-Pad8)") (class "Default")
      (node (ref "X5") (pin "8") (pinfunction "TXD_8") (pintype "bidirectional"))
    )
  )
)
